# schematic.net
KiCad netlist of a schematic drawn in EAGLE
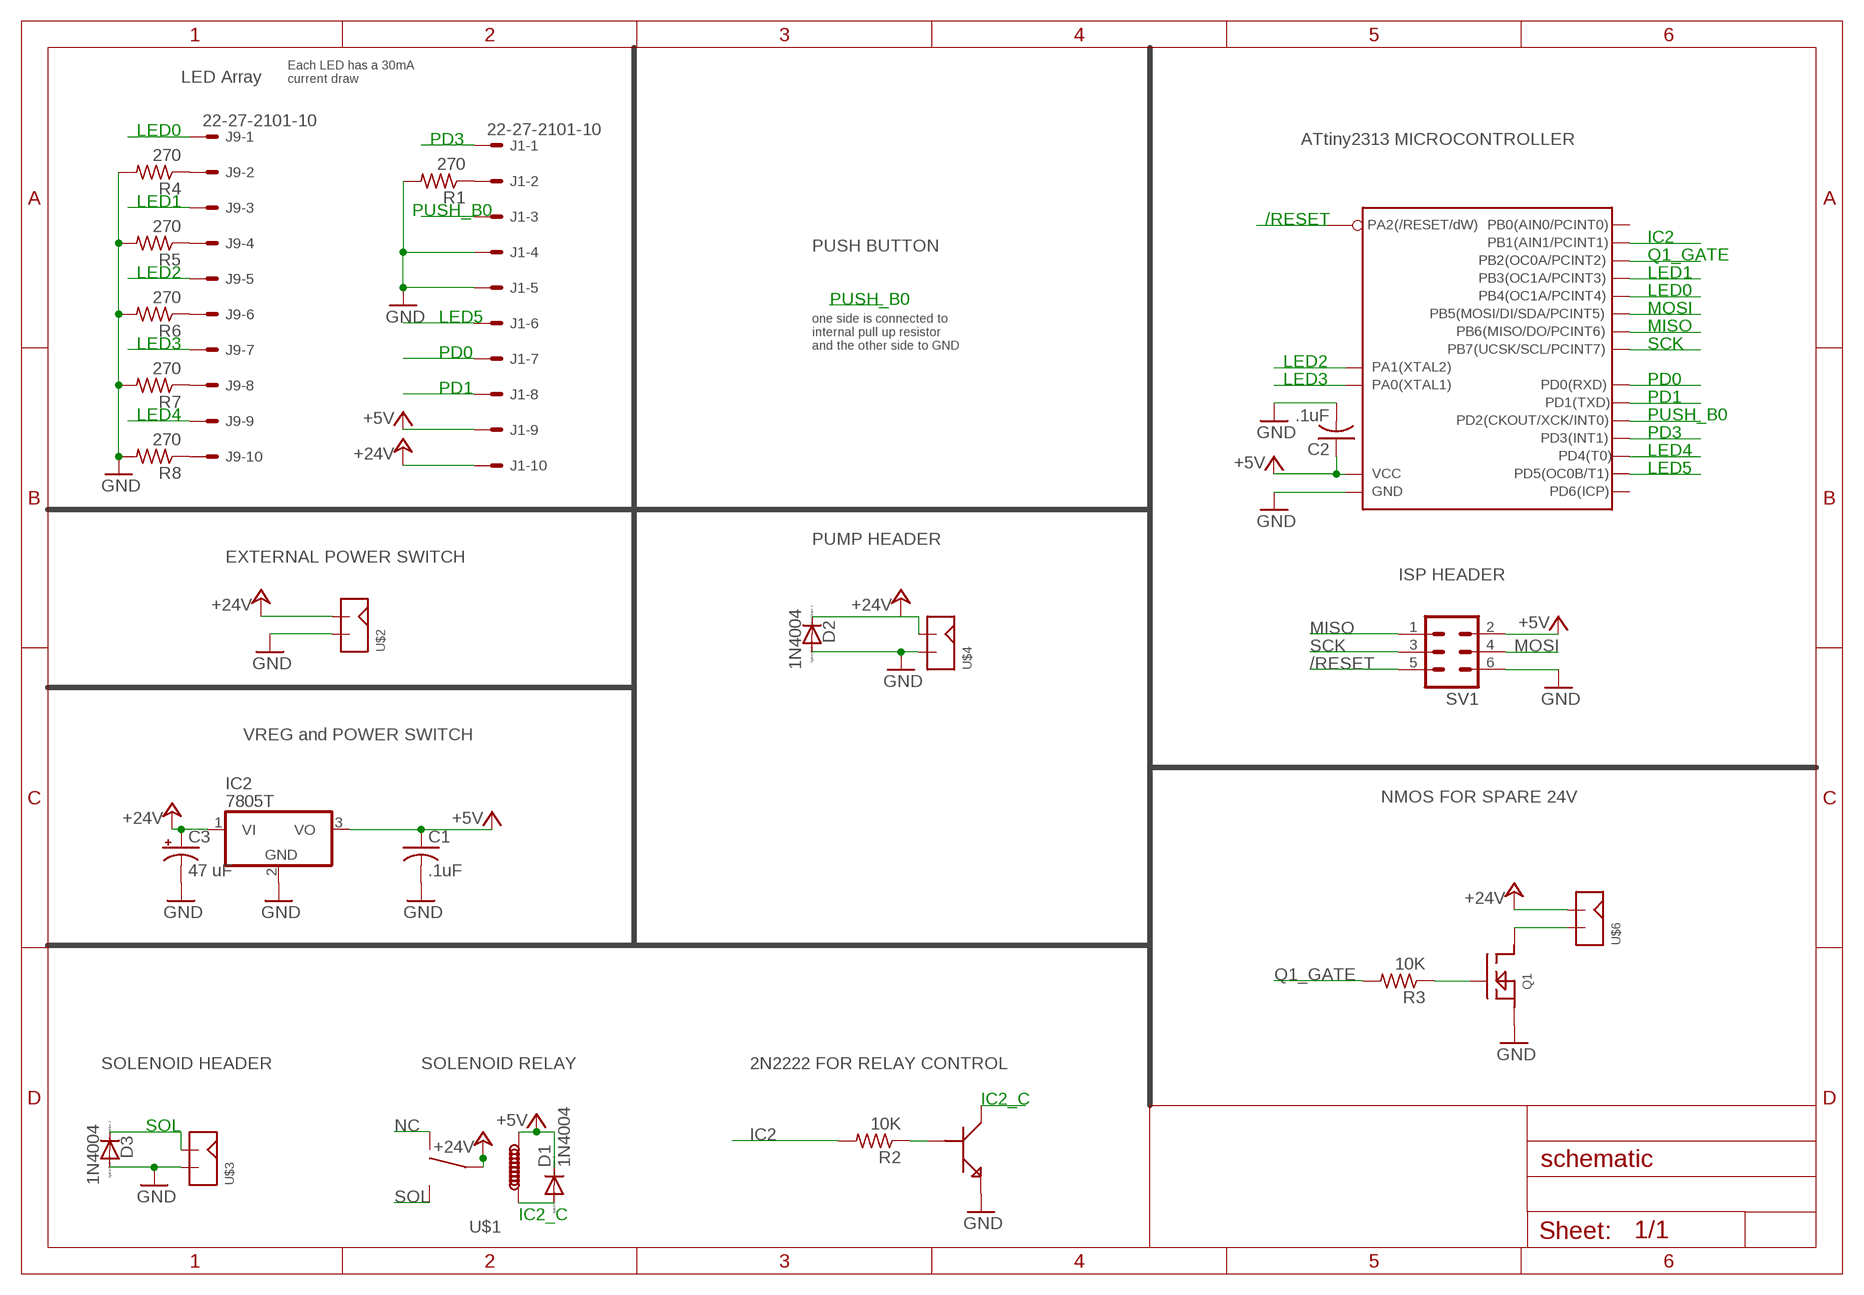
[diagram p0: schematic, sheet 1]

(export (version "E")
  (design (tool "Eeschema 10.0.6"))
  (components
    (comp (ref "C1")
      (value ".1uF")
      (footprint "eagle-import:C050-025X075")
      (libsource (lib "eagle-import") (part "C-US050-025X075"))
    )
    (comp (ref "C2")
      (value ".1uF")
      (footprint "eagle-import:C050-025X075")
      (libsource (lib "eagle-import") (part "C-US050-025X075"))
    )
    (comp (ref "C3")
      (value "47 uF")
      (footprint "eagle-import:B45181B")
      (libsource (lib "eagle-import") (part "CPOL-USB45181B"))
    )
    (comp (ref "D1")
      (value "1N4004")
      (footprint "eagle-import:DO41-10")
      (libsource (lib "eagle-import") (part "1N4004"))
    )
    (comp (ref "D2")
      (value "1N4004")
      (footprint "eagle-import:DO41-10")
      (libsource (lib "eagle-import") (part "1N4004"))
    )
    (comp (ref "D3")
      (value "1N4004")
      (footprint "eagle-import:DO41-10")
      (libsource (lib "eagle-import") (part "1N4004"))
    )
    (comp (ref "IC2")
      (value "7805T")
      (footprint "eagle-import:TO220H")
      (libsource (lib "eagle-import") (part "78T05"))
    )
    (comp (ref "J1")
      (value "22-27-2101-10")
      (footprint "eagle-import:6410-10")
      (libsource (lib "eagle-import") (part "22-?-1027-2101"))
    )
    (comp (ref "J9")
      (value "22-27-2101-10")
      (footprint "eagle-import:6410-10")
      (libsource (lib "eagle-import") (part "22-?-1027-2101"))
    )
    (comp (ref "Q1")
      (value "IRLD120")
      (footprint "eagle-import:HVMDIP")
      (libsource (lib "eagle-import") (part "IRLD120"))
    )
    (comp (ref "R1")
      (value "270")
      (footprint "eagle-import:0204_7")
      (libsource (lib "eagle-import") (part "R-US_0204/7"))
    )
    (comp (ref "R2")
      (value "10K")
      (footprint "eagle-import:0204_7")
      (libsource (lib "eagle-import") (part "R-US_0204/7"))
    )
    (comp (ref "R3")
      (value "10K")
      (footprint "eagle-import:0204_7")
      (libsource (lib "eagle-import") (part "R-US_0204/7"))
    )
    (comp (ref "R4")
      (value "270")
      (footprint "eagle-import:0204_7")
      (libsource (lib "eagle-import") (part "R-US_0204/7"))
    )
    (comp (ref "R5")
      (value "270")
      (footprint "eagle-import:0204_7")
      (libsource (lib "eagle-import") (part "R-US_0204/7"))
    )
    (comp (ref "R6")
      (value "270")
      (footprint "eagle-import:0204_7")
      (libsource (lib "eagle-import") (part "R-US_0204/7"))
    )
    (comp (ref "R7")
      (value "270")
      (footprint "eagle-import:0204_7")
      (libsource (lib "eagle-import") (part "R-US_0204/7"))
    )
    (comp (ref "R8")
      (value "270")
      (footprint "eagle-import:0204_7")
      (libsource (lib "eagle-import") (part "R-US_0204/7"))
    )
    (comp (ref "SV1")
      (value "MA03-2")
      (footprint "eagle-import:MA03-2")
      (libsource (lib "eagle-import") (part "MA03-2"))
    )
    (comp (ref "U$1")
      (value "JS1A-B-5V")
      (footprint "eagle-import:JS1A-B-5V")
      (libsource (lib "eagle-import") (part "JS1A-B-5V"))
    )
    (comp (ref "U$2")
      (value "644752_2")
      (footprint "eagle-import:644752-2")
      (libsource (lib "eagle-import") (part "644752_2"))
    )
    (comp (ref "U$3")
      (value "644752_2")
      (footprint "eagle-import:644752-2")
      (libsource (lib "eagle-import") (part "644752_2"))
    )
    (comp (ref "U$4")
      (value "644752_2")
      (footprint "eagle-import:644752-2")
      (libsource (lib "eagle-import") (part "644752_2"))
    )
    (comp (ref "U$5")
      (value "P2N2222A")
      (footprint "eagle-import:P2N2222A")
      (libsource (lib "eagle-import") (part "P2N2222A"))
    )
    (comp (ref "U$6")
      (value "644752_2")
      (footprint "eagle-import:644752-2")
      (libsource (lib "eagle-import") (part "644752_2"))
    )
    (comp (ref "U$7")
      (value "ATTINY2313")
      (footprint "eagle-import:20_DIP_MICRO")
      (libsource (lib "eagle-import") (part "ATTINY2313"))
    )
  )
  (nets
    (net (code "1") (name "+5V") (class "Default")
      (node (ref "C1") (pin "1") (pinfunction "1_1") (pintype "passive"))
      (node (ref "C2") (pin "1") (pinfunction "1_1") (pintype "passive"))
      (node (ref "D1") (pin "C") (pinfunction "C_C") (pintype "passive"))
      (node (ref "IC2") (pin "3") (pinfunction "VO_3") (pintype "passive"))
      (node (ref "J1") (pin "9") (pinfunction "S_9") (pintype "passive"))
      (node (ref "SV1") (pin "2") (pinfunction "2_2") (pintype "passive"))
      (node (ref "U$1") (pin "VIN") (pinfunction "VIN_VIN") (pintype "bidirectional"))
      (node (ref "U$7") (pin "20") (pinfunction "20_20") (pintype "bidirectional"))
    )
    (net (code "2") (name "+24V") (class "Default")
      (node (ref "C3") (pin "+") (pinfunction "+_+") (pintype "passive"))
      (node (ref "D2") (pin "C") (pinfunction "C_C") (pintype "passive"))
      (node (ref "IC2") (pin "1") (pinfunction "VI_1") (pintype "input"))
      (node (ref "J1") (pin "10") (pinfunction "S_10") (pintype "passive"))
      (node (ref "U$1") (pin "COM") (pinfunction "COM_COM") (pintype "bidirectional"))
      (node (ref "U$2") (pin "PIN1") (pinfunction "PIN1_PIN1") (pintype "bidirectional"))
      (node (ref "U$4") (pin "PIN1") (pinfunction "PIN1_PIN1") (pintype "bidirectional"))
      (node (ref "U$6") (pin "PIN1") (pinfunction "PIN1_PIN1") (pintype "bidirectional"))
    )
    (net (code "3") (name "/IC2") (class "Default")
      (node (ref "R2") (pin "2") (pinfunction "2_2") (pintype "passive"))
      (node (ref "U$7") (pin "13") (pinfunction "13_13") (pintype "bidirectional"))
    )
    (net (code "4") (name "/IC2_C") (class "Default")
      (node (ref "D1") (pin "A") (pinfunction "A_A") (pintype "passive"))
      (node (ref "U$1") (pin "GND") (pinfunction "GND_GND") (pintype "bidirectional"))
      (node (ref "U$5") (pin "COLLECTOR") (pinfunction "COLLECTOR_COLLECTOR") (pintype "bidirectional"))
    )
    (net (code "5") (name "/LED0") (class "Default")
      (node (ref "J9") (pin "1") (pinfunction "S_1") (pintype "passive"))
      (node (ref "U$7") (pin "16") (pinfunction "16_16") (pintype "bidirectional"))
    )
    (net (code "6") (name "/LED1") (class "Default")
      (node (ref "J9") (pin "3") (pinfunction "S_3") (pintype "passive"))
      (node (ref "U$7") (pin "15") (pinfunction "15_15") (pintype "bidirectional"))
    )
    (net (code "7") (name "/LED2") (class "Default")
      (node (ref "J9") (pin "5") (pinfunction "S_5") (pintype "passive"))
      (node (ref "U$7") (pin "4") (pinfunction "4_4") (pintype "bidirectional"))
    )
    (net (code "8") (name "/LED3") (class "Default")
      (node (ref "J9") (pin "7") (pinfunction "S_7") (pintype "passive"))
      (node (ref "U$7") (pin "5") (pinfunction "5_5") (pintype "bidirectional"))
    )
    (net (code "9") (name "/LED4") (class "Default")
      (node (ref "J9") (pin "9") (pinfunction "S_9") (pintype "passive"))
      (node (ref "U$7") (pin "8") (pinfunction "8_8") (pintype "bidirectional"))
    )
    (net (code "10") (name "/LED5") (class "Default")
      (node (ref "J1") (pin "6") (pinfunction "S_6") (pintype "passive"))
      (node (ref "U$7") (pin "9") (pinfunction "9_9") (pintype "bidirectional"))
    )
    (net (code "11") (name "/MISO") (class "Default")
      (node (ref "SV1") (pin "1") (pinfunction "1_1") (pintype "passive"))
      (node (ref "U$7") (pin "18") (pinfunction "18_18") (pintype "bidirectional"))
    )
    (net (code "12") (name "/MOSI") (class "Default")
      (node (ref "SV1") (pin "4") (pinfunction "4_4") (pintype "passive"))
      (node (ref "U$7") (pin "17") (pinfunction "17_17") (pintype "bidirectional"))
    )
    (net (code "13") (name "/NC") (class "Default")
      (node (ref "U$1") (pin "N.C.") (pinfunction "NC_N.C.") (pintype "bidirectional"))
    )
    (net (code "14") (name "/PD0") (class "Default")
      (node (ref "J1") (pin "7") (pinfunction "S_7") (pintype "passive"))
      (node (ref "U$7") (pin "2") (pinfunction "2_2") (pintype "bidirectional"))
    )
    (net (code "15") (name "/PD1") (class "Default")
      (node (ref "J1") (pin "8") (pinfunction "S_8") (pintype "passive"))
      (node (ref "U$7") (pin "3") (pinfunction "3_3") (pintype "bidirectional"))
    )
    (net (code "16") (name "/PD3") (class "Default")
      (node (ref "J1") (pin "1") (pinfunction "S_1") (pintype "passive"))
      (node (ref "U$7") (pin "7") (pinfunction "7_7") (pintype "bidirectional"))
    )
    (net (code "17") (name "/PUSH_B0") (class "Default")
      (node (ref "J1") (pin "3") (pinfunction "S_3") (pintype "passive"))
      (node (ref "U$7") (pin "6") (pinfunction "6_6") (pintype "bidirectional"))
    )
    (net (code "18") (name "/Q1_GATE") (class "Default")
      (node (ref "R3") (pin "2") (pinfunction "2_2") (pintype "passive"))
      (node (ref "U$7") (pin "14") (pinfunction "14_14") (pintype "bidirectional"))
    )
    (net (code "19") (name "/SCK") (class "Default")
      (node (ref "SV1") (pin "3") (pinfunction "3_3") (pintype "passive"))
      (node (ref "U$7") (pin "19") (pinfunction "19_19") (pintype "bidirectional"))
    )
    (net (code "20") (name "/SOL") (class "Default")
      (node (ref "D3") (pin "C") (pinfunction "C_C") (pintype "passive"))
      (node (ref "U$1") (pin "N.O.") (pinfunction "NO_N.O.") (pintype "bidirectional"))
      (node (ref "U$3") (pin "PIN1") (pinfunction "PIN1_PIN1") (pintype "bidirectional"))
    )
    (net (code "21") (name "/{slash}RESET") (class "Default")
      (node (ref "SV1") (pin "5") (pinfunction "5_5") (pintype "passive"))
      (node (ref "U$7") (pin "1") (pinfunction "1_1") (pintype "bidirectional"))
    )
    (net (code "22") (name "GND") (class "Default")
      (node (ref "C1") (pin "2") (pinfunction "2_2") (pintype "passive"))
      (node (ref "C2") (pin "2") (pinfunction "2_2") (pintype "passive"))
      (node (ref "C3") (pin "-") (pinfunction "-_-") (pintype "passive"))
      (node (ref "D2") (pin "A") (pinfunction "A_A") (pintype "passive"))
      (node (ref "D3") (pin "A") (pinfunction "A_A") (pintype "passive"))
      (node (ref "IC2") (pin "2") (pinfunction "GND_2") (pintype "passive"))
      (node (ref "J1") (pin "4") (pinfunction "S_4") (pintype "passive"))
      (node (ref "J1") (pin "5") (pinfunction "S_5") (pintype "passive"))
      (node (ref "Q1") (pin "S") (pinfunction "S_S") (pintype "bidirectional"))
      (node (ref "R1") (pin "2") (pinfunction "2_2") (pintype "passive"))
      (node (ref "R4") (pin "2") (pinfunction "2_2") (pintype "passive"))
      (node (ref "R5") (pin "2") (pinfunction "2_2") (pintype "passive"))
      (node (ref "R6") (pin "2") (pinfunction "2_2") (pintype "passive"))
      (node (ref "R7") (pin "2") (pinfunction "2_2") (pintype "passive"))
      (node (ref "R8") (pin "2") (pinfunction "2_2") (pintype "passive"))
      (node (ref "SV1") (pin "6") (pinfunction "6_6") (pintype "passive"))
      (node (ref "U$2") (pin "PIN2") (pinfunction "PIN2_PIN2") (pintype "bidirectional"))
      (node (ref "U$3") (pin "PIN2") (pinfunction "PIN2_PIN2") (pintype "bidirectional"))
      (node (ref "U$4") (pin "PIN2") (pinfunction "PIN2_PIN2") (pintype "bidirectional"))
      (node (ref "U$5") (pin "EMITTER") (pinfunction "EMITTER_EMITTER") (pintype "bidirectional"))
      (node (ref "U$7") (pin "10") (pinfunction "10_10") (pintype "bidirectional"))
    )
    (net (code "23") (name "Net-(J1C-S)") (class "Default")
      (node (ref "J1") (pin "2") (pinfunction "S_2") (pintype "passive"))
      (node (ref "R1") (pin "1") (pinfunction "1_1") (pintype "passive"))
    )
    (net (code "24") (name "Net-(J9B-S)") (class "Default")
      (node (ref "J9") (pin "10") (pinfunction "S_10") (pintype "passive"))
      (node (ref "R8") (pin "1") (pinfunction "1_1") (pintype "passive"))
    )
    (net (code "25") (name "Net-(J9C-S)") (class "Default")
      (node (ref "J9") (pin "2") (pinfunction "S_2") (pintype "passive"))
      (node (ref "R4") (pin "1") (pinfunction "1_1") (pintype "passive"))
    )
    (net (code "26") (name "Net-(J9E-S)") (class "Default")
      (node (ref "J9") (pin "4") (pinfunction "S_4") (pintype "passive"))
      (node (ref "R5") (pin "1") (pinfunction "1_1") (pintype "passive"))
    )
    (net (code "27") (name "Net-(J9G-S)") (class "Default")
      (node (ref "J9") (pin "6") (pinfunction "S_6") (pintype "passive"))
      (node (ref "R6") (pin "1") (pinfunction "1_1") (pintype "passive"))
    )
    (net (code "28") (name "Net-(J9I-S)") (class "Default")
      (node (ref "J9") (pin "8") (pinfunction "S_8") (pintype "passive"))
      (node (ref "R7") (pin "1") (pinfunction "1_1") (pintype "passive"))
    )
    (net (code "29") (name "Net-(Q1-D-PadD2)") (class "Default")
      (node (ref "Q1") (pin "D") (pinfunction "D_D") (pintype "bidirectional"))
      (node (ref "Q1") (pin "D2") (pinfunction "D_D2") (pintype "bidirectional"))
      (node (ref "U$6") (pin "PIN2") (pinfunction "PIN2_PIN2") (pintype "bidirectional"))
    )
    (net (code "30") (name "Net-(Q1-PadG)") (class "Default")
      (node (ref "Q1") (pin "G") (pinfunction "G_G") (pintype "bidirectional"))
      (node (ref "R3") (pin "1") (pinfunction "1_1") (pintype "passive"))
    )
    (net (code "31") (name "Net-(R2-Pad1)") (class "Default")
      (node (ref "R2") (pin "1") (pinfunction "1_1") (pintype "passive"))
      (node (ref "U$5") (pin "BASE") (pinfunction "BASE_BASE") (pintype "bidirectional"))
    )
    (net (code "32") (name "unconnected-(U$7-Pad11)") (class "Default")
      (node (ref "U$7") (pin "11") (pinfunction "11_11") (pintype "bidirectional"))
    )
    (net (code "33") (name "unconnected-(U$7-Pad12)") (class "Default")
      (node (ref "U$7") (pin "12") (pinfunction "12_12") (pintype "bidirectional"))
    )
  )
)
